# 1_-_RING_BAND.net
KiCad netlist of a schematic drawn in Altium Designer
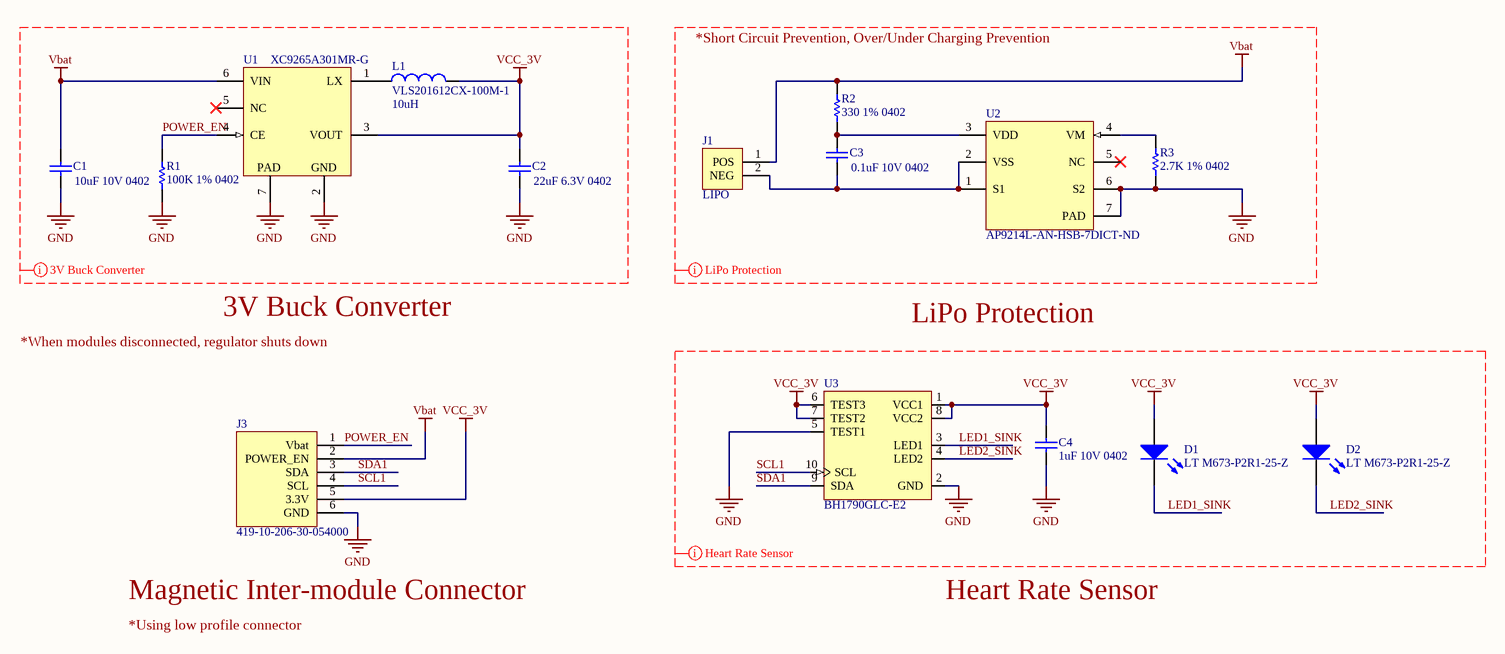
[diagram p0: [1] - RING BAND.SchDoc]

(export (version "E")
  (design (tool "Eeschema 10.0.6"))
  (components
    (comp (ref "C1")
      (value "10uF 10V 0402")
      (footprint "0402 Capacitor")
      (description "Capacitor")
      (fields (field (name "Comment") "Cap") (field (name "PUBLISHER") "Altium Limited"))
      (libsource (lib "Miscellaneous Devices") (part "Cap"))
    )
    (comp (ref "C2")
      (value "22uF 6.3V 0402")
      (footprint "0402 Capacitor")
      (description "Capacitor")
      (fields (field (name "Comment") "Cap") (field (name "PUBLISHER") "Altium Limited"))
      (libsource (lib "Miscellaneous Devices") (part "Cap"))
    )
    (comp (ref "C3")
      (value "0.1uF 10V 0402")
      (footprint "0402 Capacitor")
      (description "Capacitor")
      (fields (field (name "Comment") "Cap") (field (name "PUBLISHER") "Altium Limited"))
      (libsource (lib "Miscellaneous Devices") (part "Cap"))
    )
    (comp (ref "C4")
      (value "1uF 10V 0402")
      (footprint "0402 CAP BOT")
      (description "Capacitor")
      (fields (field (name "Comment") "Cap") (field (name "PUBLISHER") "Altium Limited"))
      (libsource (lib "Miscellaneous Devices") (part "Cap"))
    )
    (comp (ref "D1")
      (value "LT M673-P2R1-25-Z")
      (footprint "LT M673-P2R1-25-Z")
      (description "Typical RED GaAs LED")
      (fields (field (name "PUBLISHER") "Altium Limited"))
      (libsource (lib "Miscellaneous Devices") (part "LED1"))
    )
    (comp (ref "D2")
      (value "LT M673-P2R1-25-Z")
      (footprint "LT M673-P2R1-25-Z")
      (description "Typical RED GaAs LED")
      (fields (field (name "PUBLISHER") "Altium Limited"))
      (libsource (lib "Miscellaneous Devices") (part "LED1"))
    )
    (comp (ref "J1") (value "LIPO") (footprint "LIPO") (libsource (lib "Modular_Ring") (part "LIPO")))
    (comp (ref "J3")
      (value "419-10-206-30-054000")
      (footprint "419-10-206-30-007000")
      (libsource (lib "Modular_Ring") (part "419-10-206-30-007000"))
    )
    (comp (ref "L1")
      (value "VLS201612CX-100M-1")
      (footprint "VLS201612CX-100M-1")
      (description "Inductor")
      (fields (field (name "ALTIUM_VALUE") "10uH") (field (name "PUBLISHER") "Altium Limited"))
      (libsource (lib "Miscellaneous Devices") (part "Inductor"))
    )
    (comp (ref "R1")
      (value "100K 1% 0402")
      (footprint "0402 RESISTOR")
      (description "Resistor")
      (fields (field (name "Comment") "Res1") (field (name "PUBLISHER") "Altium Limited"))
      (libsource (lib "Miscellaneous Devices") (part "Res1"))
    )
    (comp (ref "R2")
      (value "330 1% 0402")
      (footprint "0402 RESISTOR")
      (description "Resistor")
      (fields (field (name "Comment") "Res1") (field (name "PUBLISHER") "Altium Limited"))
      (libsource (lib "Miscellaneous Devices") (part "Res1"))
    )
    (comp (ref "R3")
      (value "2.7K 1% 0402")
      (footprint "0402 RESISTOR")
      (description "Resistor")
      (fields (field (name "Comment") "Res1") (field (name "PUBLISHER") "Altium Limited"))
      (libsource (lib "Miscellaneous Devices") (part "Res1"))
    )
    (comp (ref "U1")
      (value "XC9265A301MR-G")
      (footprint "XC9265A3014R-G")
      (libsource (lib "Modular_Ring") (part "XC9265A3014R-G"))
    )
    (comp (ref "U2")
      (value "AP9214L-AN-HSB-7DICT-ND")
      (footprint "AP9214L-AN-HSB-7DICT-ND")
      (libsource (lib "Modular_Ring") (part "AP9214L-AN-HSB-7DICT-ND"))
    )
    (comp (ref "U3")
      (value "BH1790GLC-E2")
      (footprint "BH1790GLC-E2")
      (libsource (lib "Modular_Ring") (part "BH1790GLC-E2"))
    )
  )
  (nets
    (net (code "1") (name "/LED1_SINK") (class "Default")
      (node (ref "D1") (pin "2") (pinfunction "K_2") (pintype "passive"))
      (node (ref "U3") (pin "3") (pinfunction "LED1_3") (pintype "passive"))
    )
    (net (code "2") (name "/LED2_SINK") (class "Default")
      (node (ref "D2") (pin "2") (pinfunction "K_2") (pintype "passive"))
      (node (ref "U3") (pin "4") (pinfunction "LED2_4") (pintype "passive"))
    )
    (net (code "3") (name "/POWER_EN") (class "Default")
      (node (ref "J3") (pin "1") (pinfunction "Vbat_1") (pintype "passive"))
      (node (ref "R1") (pin "1") (pinfunction "1_1") (pintype "passive"))
      (node (ref "U1") (pin "4") (pinfunction "CE_4") (pintype "input"))
    )
    (net (code "4") (name "/SCL1") (class "Default")
      (node (ref "J3") (pin "4") (pinfunction "SCL_4") (pintype "passive"))
      (node (ref "U3") (pin "10") (pinfunction "SCL_10") (pintype "input"))
    )
    (net (code "5") (name "/SDA1") (class "Default")
      (node (ref "J3") (pin "3") (pinfunction "SDA_3") (pintype "passive"))
      (node (ref "U3") (pin "9") (pinfunction "SDA_9") (pintype "bidirectional"))
    )
    (net (code "6") (name "GND") (class "Default")
      (node (ref "C1") (pin "1") (pinfunction "1_1") (pintype "passive"))
      (node (ref "C2") (pin "1") (pinfunction "1_1") (pintype "passive"))
      (node (ref "C4") (pin "2") (pinfunction "2_2") (pintype "passive"))
      (node (ref "J3") (pin "6") (pinfunction "GND_6") (pintype "passive"))
      (node (ref "R1") (pin "2") (pinfunction "2_2") (pintype "passive"))
      (node (ref "R3") (pin "1") (pinfunction "1_1") (pintype "passive"))
      (node (ref "U1") (pin "2") (pinfunction "GND_2") (pintype "power_in"))
      (node (ref "U1") (pin "7") (pinfunction "GND_7") (pintype "power_in"))
      (node (ref "U2") (pin "6") (pinfunction "S2_6") (pintype "power_in"))
      (node (ref "U2") (pin "7") (pinfunction "PAD_7") (pintype "passive"))
      (node (ref "U3") (pin "2") (pinfunction "GND_2") (pintype "power_in"))
      (node (ref "U3") (pin "5") (pinfunction "TEST1_5") (pintype "passive"))
    )
    (net (code "7") (name "Net-(J1-NEG)") (class "Default")
      (node (ref "C3") (pin "1") (pinfunction "1_1") (pintype "passive"))
      (node (ref "J1") (pin "2") (pinfunction "NEG_2") (pintype "passive"))
      (node (ref "U2") (pin "1") (pinfunction "S1_1") (pintype "power_in"))
      (node (ref "U2") (pin "2") (pinfunction "VSS_2") (pintype "passive"))
    )
    (net (code "8") (name "Net-(U1-LX)") (class "Default")
      (node (ref "L1") (pin "1") (pinfunction "1_1") (pintype "passive"))
      (node (ref "U1") (pin "1") (pinfunction "LX_1") (pintype "power_in"))
    )
    (net (code "9") (name "Net-(U2-VDD)") (class "Default")
      (node (ref "C3") (pin "2") (pinfunction "2_2") (pintype "passive"))
      (node (ref "R2") (pin "2") (pinfunction "2_2") (pintype "passive"))
      (node (ref "U2") (pin "3") (pinfunction "VDD_3") (pintype "passive"))
    )
    (net (code "10") (name "Net-(U2-VM)") (class "Default")
      (node (ref "R3") (pin "2") (pinfunction "2_2") (pintype "passive"))
      (node (ref "U2") (pin "4") (pinfunction "VM_4") (pintype "input"))
    )
    (net (code "11") (name "VCC_3V") (class "Default")
      (node (ref "C2") (pin "2") (pinfunction "2_2") (pintype "passive"))
      (node (ref "C4") (pin "1") (pinfunction "1_1") (pintype "passive"))
      (node (ref "D1") (pin "1") (pinfunction "A_1") (pintype "passive"))
      (node (ref "D2") (pin "1") (pinfunction "A_1") (pintype "passive"))
      (node (ref "J3") (pin "5") (pinfunction "3.3V_5") (pintype "passive"))
      (node (ref "L1") (pin "2") (pinfunction "2_2") (pintype "passive"))
      (node (ref "U1") (pin "3") (pinfunction "VOUT_3") (pintype "power_in"))
      (node (ref "U3") (pin "1") (pinfunction "VCC1_1") (pintype "power_in"))
      (node (ref "U3") (pin "6") (pinfunction "TEST3_6") (pintype "passive"))
      (node (ref "U3") (pin "7") (pinfunction "TEST2_7") (pintype "passive"))
      (node (ref "U3") (pin "8") (pinfunction "VCC2_8") (pintype "power_in"))
    )
    (net (code "12") (name "Vbat") (class "Default")
      (node (ref "C1") (pin "2") (pinfunction "2_2") (pintype "passive"))
      (node (ref "J1") (pin "1") (pinfunction "POS_1") (pintype "passive"))
      (node (ref "J3") (pin "2") (pinfunction "POWER_EN_2") (pintype "passive"))
      (node (ref "R2") (pin "1") (pinfunction "1_1") (pintype "passive"))
      (node (ref "U1") (pin "6") (pinfunction "VIN_6") (pintype "power_in"))
    )
    (net (code "13") (name "unconnected-(U1-NC-Pad5)") (class "Default")
      (node (ref "U1") (pin "5") (pinfunction "NC_5") (pintype "passive+no_connect"))
    )
    (net (code "14") (name "unconnected-(U2-NC-Pad5)") (class "Default")
      (node (ref "U2") (pin "5") (pinfunction "NC_5") (pintype "passive+no_connect"))
    )
  )
)
